# not_sure_yet.net
KiCad netlist of a schematic drawn in Altium Designer
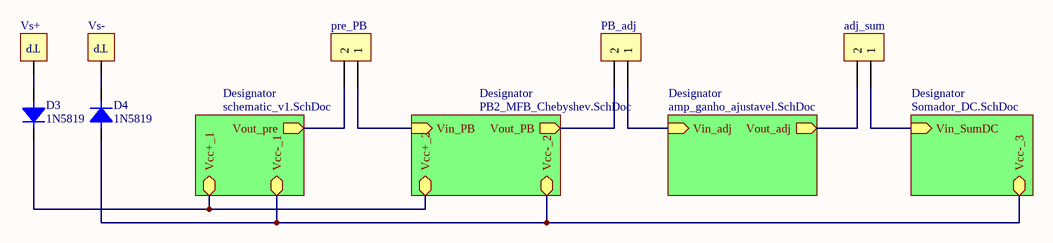
[diagram p0: not_sure_yet.SchDoc]

(export (version "E")
  (design (tool "Eeschema 10.0.6"))
  (components
    (comp (ref "adj_sum")
      (value "Header_1x2")
      (footprint "HDR-M-1x2-2.54mm-180-9.2mm")
      (description "Header, 1 Line, 2 Columns, 2 Pins")
      (fields (field (name "PUBLISHER") "Altium Limited"))
      (libsource (lib "GPDSE") (part "Header_1x2"))
    )
    (comp (ref "D3")
      (value "1N5819")
      (footprint "DO-41-Plastic")
      (description "General Purpose Rectifier")
      (libsource (lib "GPDSE") (part "1N4007"))
    )
    (comp (ref "D4")
      (value "1N5819")
      (footprint "DO-41-Plastic")
      (description "General Purpose Rectifier")
      (libsource (lib "GPDSE") (part "1N4007"))
    )
    (comp (ref "PB_adj")
      (value "Header_1x2")
      (footprint "HDR-M-1x2-2.54mm-180-9.2mm")
      (description "Header, 1 Line, 2 Columns, 2 Pins")
      (fields (field (name "PUBLISHER") "Altium Limited"))
      (libsource (lib "GPDSE") (part "Header_1x2"))
    )
    (comp (ref "pre_PB")
      (value "Header_1x2")
      (footprint "HDR-M-1x2-2.54mm-180-9.2mm")
      (description "Header, 1 Line, 2 Columns, 2 Pins")
      (fields (field (name "PUBLISHER") "Altium Limited"))
      (libsource (lib "GPDSE") (part "Header_1x2"))
    )
    (comp (ref "Vs+")
      (value "TestPoint")
      (footprint "TEST_POINT_PTH")
      (description "Test Point")
      (libsource (lib "GPDSE") (part "TestPoint"))
    )
    (comp (ref "Vs-")
      (value "TestPoint")
      (footprint "TEST_POINT_PTH")
      (description "Test Point")
      (libsource (lib "GPDSE") (part "TestPoint"))
    )
  )
  (nets
    (net (code "1") (name "/Vcc+_1") (class "Default")
      (node (ref "D3") (pin "K") (pinfunction "K_K") (pintype "passive"))
    )
    (net (code "2") (name "/Vcc-_1") (class "Default")
      (node (ref "D4") (pin "A") (pinfunction "A_A") (pintype "passive"))
    )
    (net (code "3") (name "/Vin_PB") (class "Default")
      (node (ref "pre_PB") (pin "1") (pinfunction "1_1") (pintype "passive"))
    )
    (net (code "4") (name "/Vin_SumDC") (class "Default")
      (node (ref "adj_sum") (pin "1") (pinfunction "1_1") (pintype "passive"))
    )
    (net (code "5") (name "/Vin_adj") (class "Default")
      (node (ref "PB_adj") (pin "1") (pinfunction "1_1") (pintype "passive"))
    )
    (net (code "6") (name "/Vout_PB") (class "Default")
      (node (ref "PB_adj") (pin "2") (pinfunction "2_2") (pintype "passive"))
    )
    (net (code "7") (name "/Vout_adj") (class "Default")
      (node (ref "adj_sum") (pin "2") (pinfunction "2_2") (pintype "passive"))
    )
    (net (code "8") (name "/Vout_pre") (class "Default")
      (node (ref "pre_PB") (pin "2") (pinfunction "2_2") (pintype "passive"))
    )
    (net (code "9") (name "Net-(Vs+-TP)") (class "Default")
      (node (ref "D3") (pin "A") (pinfunction "A_A") (pintype "passive"))
      (node (ref "Vs+") (pin "1") (pinfunction "TP_1") (pintype "passive"))
    )
    (net (code "10") (name "Net-(Vs--TP)") (class "Default")
      (node (ref "D4") (pin "K") (pinfunction "K_K") (pintype "passive"))
      (node (ref "Vs-") (pin "1") (pinfunction "TP_1") (pintype "passive"))
    )
  )
)
